# DS18B20.net
KiCad netlist of a schematic drawn in Altium Designer
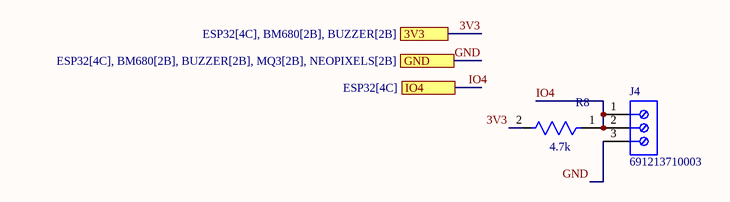
[diagram p0: DS18B20.SchDoc]

(export (version "E")
  (design (tool "Eeschema 10.0.6"))
  (components
    (comp (ref "J4")
      (value "691213710003")
      (footprint "691213710003")
      (fields (field (name "VOLTAGE") "300V"))
      (libsource (lib "Altium Content Vault") (part "TBL - 1R - 03P - Screw"))
    )
    (comp (ref "R8")
      (value "4.7k")
      (footprint "FP-ERA6A-IPC_B")
      (description "RES 100K OHM 0.1% 1/8W 0805")
      (fields (field (name "TOLERANCE") "0.1%"))
      (libsource (lib "Altium Content Vault") (part "1029c3af85768c4190bb7ad29bc67b5"))
    )
  )
  (nets
    (net (code "1") (name "/3V3") (class "Default")
      (node (ref "R8") (pin "2") (pinfunction "2_2") (pintype "passive"))
    )
    (net (code "2") (name "/GND") (class "Default")
      (node (ref "J4") (pin "3") (pinfunction "3_3") (pintype "passive"))
    )
    (net (code "3") (name "/IO4") (class "Default")
      (node (ref "J4") (pin "1") (pinfunction "1_1") (pintype "passive"))
      (node (ref "J4") (pin "2") (pinfunction "2_2") (pintype "passive"))
      (node (ref "R8") (pin "1") (pinfunction "1_1") (pintype "passive"))
    )
  )
)
